# openSX70-dongle_v4-push.net
KiCad netlist of a schematic drawn in EAGLE
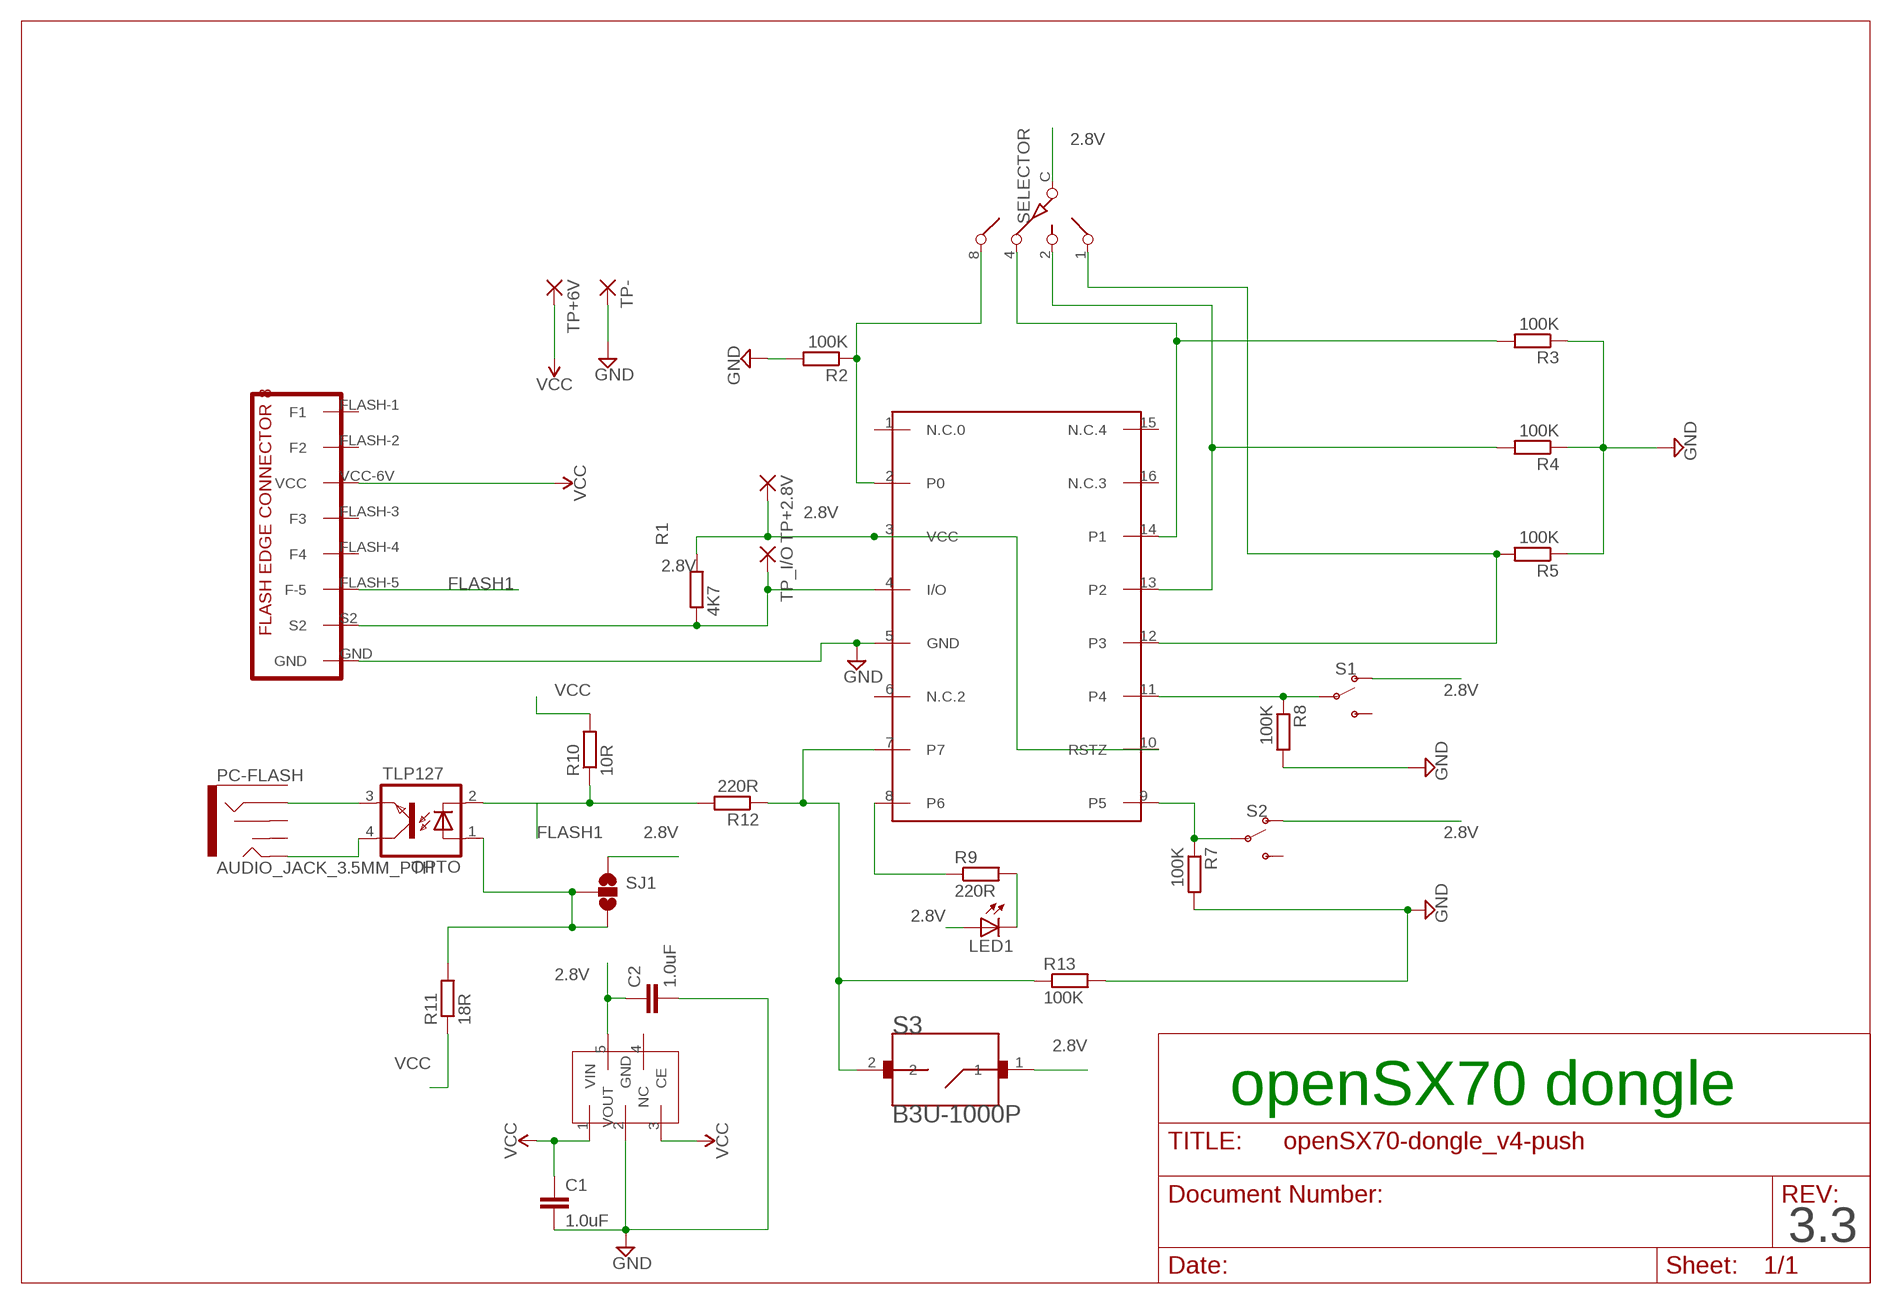
[diagram p0: schematic, sheet 1]

(export (version "E")
  (design (tool "Eeschema 10.0.6"))
  (components
    (comp (ref "C1")
      (value "1.0uF")
      (footprint "eagle-import:C0603")
      (libsource (lib "eagle-import") (part "C-EUC0603"))
    )
    (comp (ref "C2")
      (value "1.0uF")
      (footprint "eagle-import:C0603")
      (libsource (lib "eagle-import") (part "C-EUC0603"))
    )
    (comp (ref "DS2408")
      (value "DS2408")
      (footprint "eagle-import:SO16")
      (libsource (lib "eagle-import") (part "DS2408"))
    )
    (comp (ref "LED1")
      (value "LED3MM")
      (footprint "eagle-import:LED3MM")
      (libsource (lib "eagle-import") (part "LED3MM"))
    )
    (comp (ref "OPTO")
      (value "TLP127")
      (footprint "eagle-import:SO-4")
      (libsource (lib "eagle-import") (part "TLP127"))
    )
    (comp (ref "PC-FLASH")
      (value "AUDIO_JACK_3.5MM_PTH")
      (footprint "eagle-import:AUDIO-JACK")
      (libsource (lib "eagle-import") (part "AUDIO_JACK_3.5MM_PTH"))
    )
    (comp (ref "R1")
      (value "4K7")
      (footprint "eagle-import:R0603")
      (libsource (lib "eagle-import") (part "R-EU_R0603"))
    )
    (comp (ref "R2")
      (value "100K")
      (footprint "eagle-import:R0603")
      (libsource (lib "eagle-import") (part "R-EU_R0603"))
    )
    (comp (ref "R3")
      (value "100K")
      (footprint "eagle-import:R0603")
      (libsource (lib "eagle-import") (part "R-EU_R0603"))
    )
    (comp (ref "R4")
      (value "100K")
      (footprint "eagle-import:R0603")
      (libsource (lib "eagle-import") (part "R-EU_R0603"))
    )
    (comp (ref "R5")
      (value "100K")
      (footprint "eagle-import:R0603")
      (libsource (lib "eagle-import") (part "R-EU_R0603"))
    )
    (comp (ref "R7")
      (value "100K")
      (footprint "eagle-import:R0603")
      (libsource (lib "eagle-import") (part "R-EU_R0603"))
    )
    (comp (ref "R8")
      (value "100K")
      (footprint "eagle-import:R0603")
      (libsource (lib "eagle-import") (part "R-EU_R0603"))
    )
    (comp (ref "R9")
      (value "220R")
      (footprint "eagle-import:R0603")
      (libsource (lib "eagle-import") (part "R-EU_R0603"))
    )
    (comp (ref "R10")
      (value "10R")
      (footprint "eagle-import:R0603")
      (libsource (lib "eagle-import") (part "resistor_348_R-EU_R0603"))
    )
    (comp (ref "R11")
      (value "18R")
      (footprint "eagle-import:R0603")
      (libsource (lib "eagle-import") (part "resistor_348_R-EU_R0603"))
    )
    (comp (ref "R12")
      (value "220R")
      (footprint "eagle-import:R0603")
      (libsource (lib "eagle-import") (part "R-EU_R0603"))
    )
    (comp (ref "R13")
      (value "100K")
      (footprint "eagle-import:R0603")
      (libsource (lib "eagle-import") (part "R-EU_R0603"))
    )
    (comp (ref "REG")
      (value "NCP4688")
      (footprint "eagle-import:SOT-23-5")
      (libsource (lib "eagle-import") (part "NCP4688"))
    )
    (comp (ref "S1")
      (value "SWITCH-SPDT-SMD-RIGHT-ANGLE")
      (footprint "eagle-import:SWITCH_SPST_SMD_A")
      (libsource (lib "eagle-import") (part "SWITCH-SPDT-SMD-RIGHT-ANGLE"))
    )
    (comp (ref "S2")
      (value "SWITCH-SPDT-SMD-RIGHT-ANGLE")
      (footprint "eagle-import:SWITCH_SPST_SMD_A")
      (libsource (lib "eagle-import") (part "SWITCH-SPDT-SMD-RIGHT-ANGLE"))
    )
    (comp (ref "S3")
      (value "B3U-1000P")
      (footprint "eagle-import:SW_B3U-1000P")
      (fields (field (name "MANUFACTURER") "Omron"))
      (libsource (lib "eagle-import") (part "B3U-1000P"))
    )
    (comp (ref "SELECTOR")
      (value "SW-C16")
      (footprint "eagle-import:SW-C16")
      (libsource (lib "eagle-import") (part "SW-C16"))
    )
    (comp (ref "SJ1")
      (value "SOLDERJUMPER_2WAYS")
      (footprint "eagle-import:SJ_3")
      (libsource (lib "eagle-import") (part "SOLDERJUMPER_2WAYS"))
    )
    (comp (ref "TP+2.8V")
      (value "SMD2")
      (footprint "eagle-import:SMD1,27-2,54")
      (libsource (lib "eagle-import") (part "SMD2"))
    )
    (comp (ref "TP+6V")
      (value "SMD2")
      (footprint "eagle-import:SMD1,27-2,54")
      (libsource (lib "eagle-import") (part "SMD2"))
    )
    (comp (ref "TP-")
      (value "SMD2")
      (footprint "eagle-import:SMD1,27-2,54")
      (libsource (lib "eagle-import") (part "SMD2"))
    )
    (comp (ref "TP_I/O")
      (value "SMD2")
      (footprint "eagle-import:SMD1,27-2,54")
      (libsource (lib "eagle-import") (part "SMD2"))
    )
    (comp (ref "U$2")
      (value "SX70-FLASH-EDGE8-MALE-PROPER")
      (footprint "eagle-import:SX70-FLASH-EDGE8")
      (libsource (lib "eagle-import") (part "SX70-FLASH-EDGE8-MALE-PROPER"))
    )
  )
  (nets
    (net (code "1") (name "/2.8V") (class "Default")
      (node (ref "C2") (pin "1") (pinfunction "1_1") (pintype "passive"))
      (node (ref "DS2408") (pin "10") (pinfunction "RSTZ_10") (pintype "bidirectional"))
      (node (ref "DS2408") (pin "3") (pinfunction "VCC_3") (pintype "bidirectional"))
      (node (ref "LED1") (pin "A") (pinfunction "A_A") (pintype "passive"))
      (node (ref "R1") (pin "2") (pinfunction "2_2") (pintype "passive"))
      (node (ref "REG") (pin "5") (pinfunction "VOUT_5") (pintype "bidirectional"))
      (node (ref "S1") (pin "1") (pinfunction "O_1") (pintype "passive"))
      (node (ref "S2") (pin "1") (pinfunction "O_1") (pintype "passive"))
      (node (ref "S3") (pin "1") (pinfunction "1_1") (pintype "passive"))
      (node (ref "SELECTOR") (pin "C") (pinfunction "C_C") (pintype "passive"))
      (node (ref "SJ1") (pin "1") (pinfunction "1_1") (pintype "passive"))
      (node (ref "TP+2.8V") (pin "1") (pinfunction "P_1") (pintype "passive"))
    )
    (net (code "2") (name "/FLASH1") (class "Default")
      (node (ref "OPTO") (pin "1") (pinfunction "A_1") (pintype "passive"))
      (node (ref "OPTO") (pin "2") (pinfunction "C_2") (pintype "passive"))
      (node (ref "R10") (pin "1") (pinfunction "1_1") (pintype "passive"))
      (node (ref "R11") (pin "2") (pinfunction "2_2") (pintype "passive"))
      (node (ref "R12") (pin "2") (pinfunction "2_2") (pintype "passive"))
      (node (ref "SJ1") (pin "2") (pinfunction "2_2") (pintype "passive"))
      (node (ref "SJ1") (pin "3") (pinfunction "3_3") (pintype "passive"))
      (node (ref "U$2") (pin "FLASH-5") (pinfunction "F-5_FLASH-5") (pintype "bidirectional"))
    )
    (net (code "3") (name "GND") (class "Default")
      (node (ref "C1") (pin "2") (pinfunction "2_2") (pintype "passive"))
      (node (ref "C2") (pin "2") (pinfunction "2_2") (pintype "passive"))
      (node (ref "DS2408") (pin "5") (pinfunction "GND_5") (pintype "bidirectional"))
      (node (ref "R13") (pin "2") (pinfunction "2_2") (pintype "passive"))
      (node (ref "R2") (pin "2") (pinfunction "2_2") (pintype "passive"))
      (node (ref "R3") (pin "1") (pinfunction "1_1") (pintype "passive"))
      (node (ref "R4") (pin "1") (pinfunction "1_1") (pintype "passive"))
      (node (ref "R5") (pin "1") (pinfunction "1_1") (pintype "passive"))
      (node (ref "R7") (pin "2") (pinfunction "2_2") (pintype "passive"))
      (node (ref "R8") (pin "2") (pinfunction "2_2") (pintype "passive"))
      (node (ref "REG") (pin "2") (pinfunction "GND_2") (pintype "bidirectional"))
      (node (ref "TP-") (pin "1") (pinfunction "P_1") (pintype "passive"))
      (node (ref "U$2") (pin "GND") (pinfunction "GND_GND") (pintype "bidirectional"))
    )
    (net (code "4") (name "Net-(DS2408-I{slash}O)") (class "Default")
      (node (ref "DS2408") (pin "4") (pinfunction "I/O_4") (pintype "bidirectional"))
      (node (ref "R1") (pin "1") (pinfunction "1_1") (pintype "passive"))
      (node (ref "TP_I/O") (pin "1") (pinfunction "P_1") (pintype "passive"))
      (node (ref "U$2") (pin "S2") (pinfunction "S2_S2") (pintype "bidirectional"))
    )
    (net (code "5") (name "Net-(DS2408-P0)") (class "Default")
      (node (ref "DS2408") (pin "2") (pinfunction "P0_2") (pintype "bidirectional"))
      (node (ref "R2") (pin "1") (pinfunction "1_1") (pintype "passive"))
      (node (ref "SELECTOR") (pin "8") (pinfunction "8_8") (pintype "passive"))
    )
    (net (code "6") (name "Net-(DS2408-P1)") (class "Default")
      (node (ref "DS2408") (pin "14") (pinfunction "P1_14") (pintype "bidirectional"))
      (node (ref "R3") (pin "2") (pinfunction "2_2") (pintype "passive"))
      (node (ref "SELECTOR") (pin "4") (pinfunction "4_4") (pintype "passive"))
    )
    (net (code "7") (name "Net-(DS2408-P2)") (class "Default")
      (node (ref "DS2408") (pin "13") (pinfunction "P2_13") (pintype "bidirectional"))
      (node (ref "R4") (pin "2") (pinfunction "2_2") (pintype "passive"))
      (node (ref "SELECTOR") (pin "2") (pinfunction "2_2") (pintype "passive"))
    )
    (net (code "8") (name "Net-(DS2408-P3)") (class "Default")
      (node (ref "DS2408") (pin "12") (pinfunction "P3_12") (pintype "bidirectional"))
      (node (ref "R5") (pin "2") (pinfunction "2_2") (pintype "passive"))
      (node (ref "SELECTOR") (pin "1") (pinfunction "1_1") (pintype "passive"))
    )
    (net (code "9") (name "Net-(DS2408-P4)") (class "Default")
      (node (ref "DS2408") (pin "11") (pinfunction "P4_11") (pintype "bidirectional"))
      (node (ref "R8") (pin "1") (pinfunction "1_1") (pintype "passive"))
      (node (ref "S1") (pin "2") (pinfunction "P_2") (pintype "passive"))
    )
    (net (code "10") (name "Net-(DS2408-P5)") (class "Default")
      (node (ref "DS2408") (pin "9") (pinfunction "P5_9") (pintype "bidirectional"))
      (node (ref "R7") (pin "1") (pinfunction "1_1") (pintype "passive"))
      (node (ref "S2") (pin "2") (pinfunction "P_2") (pintype "passive"))
    )
    (net (code "11") (name "Net-(DS2408-P6)") (class "Default")
      (node (ref "DS2408") (pin "8") (pinfunction "P6_8") (pintype "bidirectional"))
      (node (ref "R9") (pin "1") (pinfunction "1_1") (pintype "passive"))
    )
    (net (code "12") (name "Net-(DS2408-P7)") (class "Default")
      (node (ref "DS2408") (pin "7") (pinfunction "P7_7") (pintype "bidirectional"))
      (node (ref "R12") (pin "1") (pinfunction "1_1") (pintype "passive"))
      (node (ref "R13") (pin "1") (pinfunction "1_1") (pintype "passive"))
      (node (ref "S3") (pin "2") (pinfunction "2_2") (pintype "passive"))
    )
    (net (code "13") (name "Net-(LED1-C)") (class "Default")
      (node (ref "LED1") (pin "K") (pinfunction "C_K") (pintype "passive"))
      (node (ref "R9") (pin "2") (pinfunction "2_2") (pintype "passive"))
    )
    (net (code "14") (name "Net-(OPTO-COL)") (class "Default")
      (node (ref "OPTO") (pin "4") (pinfunction "COL_4") (pintype "passive"))
      (node (ref "PC-FLASH") (pin "TIP") (pinfunction "TIP_TIP") (pintype "bidirectional"))
    )
    (net (code "15") (name "Net-(OPTO-EMIT)") (class "Default")
      (node (ref "OPTO") (pin "3") (pinfunction "EMIT_3") (pintype "passive"))
      (node (ref "PC-FLASH") (pin "RING") (pinfunction "RING_RING") (pintype "bidirectional"))
    )
    (net (code "16") (name "VCC") (class "Default")
      (node (ref "C1") (pin "1") (pinfunction "1_1") (pintype "passive"))
      (node (ref "R10") (pin "2") (pinfunction "2_2") (pintype "passive"))
      (node (ref "R11") (pin "1") (pinfunction "1_1") (pintype "passive"))
      (node (ref "REG") (pin "1") (pinfunction "VIN_1") (pintype "bidirectional"))
      (node (ref "REG") (pin "3") (pinfunction "CE_3") (pintype "bidirectional"))
      (node (ref "TP+6V") (pin "1") (pinfunction "P_1") (pintype "passive"))
      (node (ref "U$2") (pin "VCC-6V") (pinfunction "VCC_VCC-6V") (pintype "bidirectional"))
    )
    (net (code "17") (name "unconnected-(DS2408-N.C.0-Pad1)") (class "Default")
      (node (ref "DS2408") (pin "1") (pinfunction "N.C.0_1") (pintype "bidirectional"))
    )
    (net (code "18") (name "unconnected-(DS2408-N.C.2-Pad6)") (class "Default")
      (node (ref "DS2408") (pin "6") (pinfunction "N.C.2_6") (pintype "bidirectional"))
    )
    (net (code "19") (name "unconnected-(DS2408-N.C.3-Pad16)") (class "Default")
      (node (ref "DS2408") (pin "16") (pinfunction "N.C.3_16") (pintype "bidirectional"))
    )
    (net (code "20") (name "unconnected-(DS2408-N.C.4-Pad15)") (class "Default")
      (node (ref "DS2408") (pin "15") (pinfunction "N.C.4_15") (pintype "bidirectional"))
    )
    (net (code "21") (name "unconnected-(PC-FLASH-PadRSH)") (class "Default")
      (node (ref "PC-FLASH") (pin "RSH") (pinfunction "RSH_RSH") (pintype "bidirectional"))
    )
    (net (code "22") (name "unconnected-(PC-FLASH-PadSLEEVE)") (class "Default")
      (node (ref "PC-FLASH") (pin "SLEEVE") (pinfunction "SLEEVE_SLEEVE") (pintype "bidirectional"))
    )
    (net (code "23") (name "unconnected-(PC-FLASH-PadTSH)") (class "Default")
      (node (ref "PC-FLASH") (pin "TSH") (pinfunction "TSH_TSH") (pintype "bidirectional"))
    )
    (net (code "24") (name "unconnected-(REG-NC-Pad4)") (class "Default")
      (node (ref "REG") (pin "4") (pinfunction "NC_4") (pintype "bidirectional"))
    )
    (net (code "25") (name "unconnected-(S1-S-Pad3)") (class "Default")
      (node (ref "S1") (pin "3") (pinfunction "S_3") (pintype "passive"))
    )
    (net (code "26") (name "unconnected-(S2-S-Pad3)") (class "Default")
      (node (ref "S2") (pin "3") (pinfunction "S_3") (pintype "passive"))
    )
    (net (code "27") (name "unconnected-(U$2-F1-PadFLASH-1)") (class "Default")
      (node (ref "U$2") (pin "FLASH-1") (pinfunction "F1_FLASH-1") (pintype "bidirectional"))
    )
    (net (code "28") (name "unconnected-(U$2-F2-PadFLASH-2)") (class "Default")
      (node (ref "U$2") (pin "FLASH-2") (pinfunction "F2_FLASH-2") (pintype "bidirectional"))
    )
    (net (code "29") (name "unconnected-(U$2-F3-PadFLASH-3)") (class "Default")
      (node (ref "U$2") (pin "FLASH-3") (pinfunction "F3_FLASH-3") (pintype "bidirectional"))
    )
    (net (code "30") (name "unconnected-(U$2-F4-PadFLASH-4)") (class "Default")
      (node (ref "U$2") (pin "FLASH-4") (pinfunction "F4_FLASH-4") (pintype "bidirectional"))
    )
  )
)
